# LM7X05-SCH.net
KiCad netlist of a schematic drawn in Altium Designer
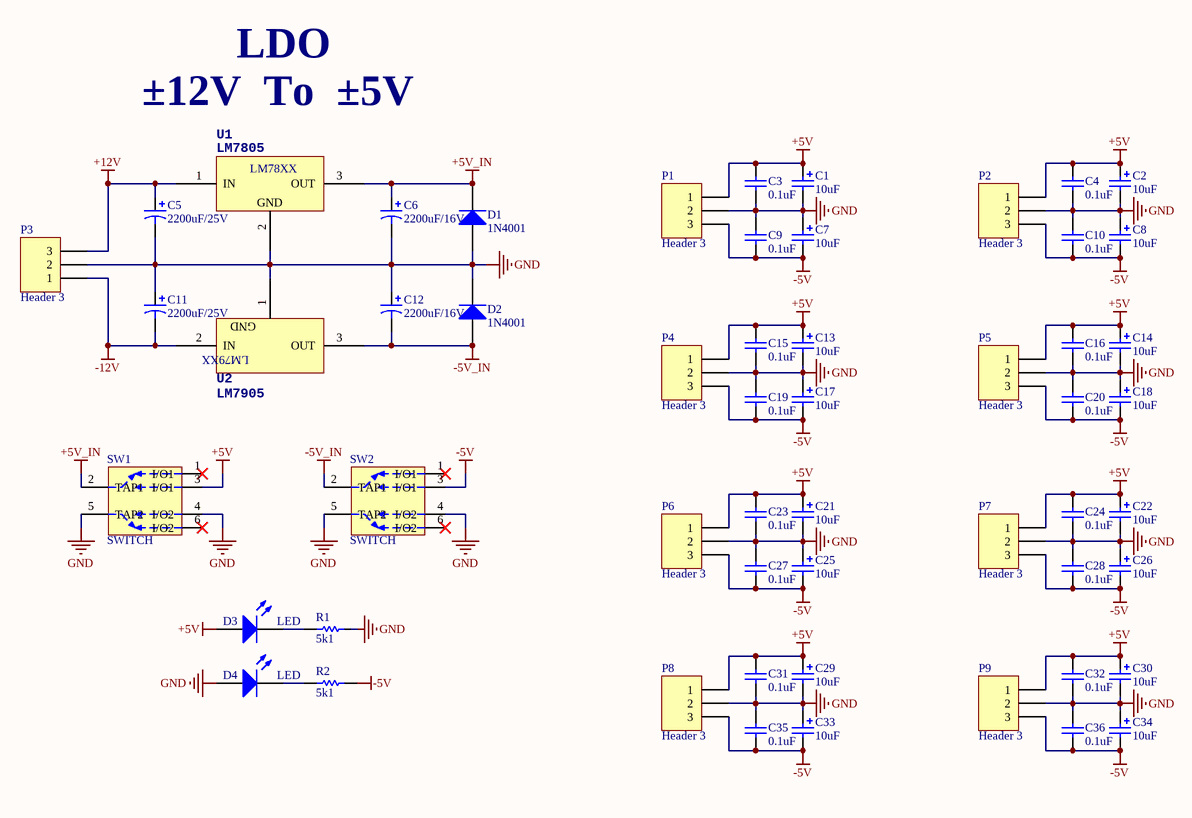
[diagram p0: LM7X05-SCH.SchDoc]

(export (version "E")
  (design (tool "Eeschema 10.0.6"))
  (components
    (comp (ref "C1")
      (value "10uF")
      (footprint "1206T")
      (description "CAP TANT 10UF 10V 10% 1206")
      (fields
        (field (name "MANUFACTURER") "KEMET")
        (field (name "MANUFACTURER PART NUMBER") "T491A106K010AT7280")
      )
      (libsource (lib "Desiger_Schlib") (part "Cap2"))
    )
    (comp (ref "C2")
      (value "10uF")
      (footprint "1206T")
      (description "CAP TANT 10UF 10V 10% 1206")
      (fields
        (field (name "MANUFACTURER") "KEMET")
        (field (name "MANUFACTURER PART NUMBER") "T491A106K010AT7280")
      )
      (libsource (lib "Desiger_Schlib") (part "Cap2"))
    )
    (comp (ref "C3")
      (value "0.1uF")
      (footprint "1206C")
      (description "CAP CER 10000PF 100V X7R 0603")
      (fields
        (field (name "MANUFACTURER") "TDK Corporation")
        (field (name "MANUFACTURER PART NUMBER") "C1608X7R2A103K080AA")
      )
      (libsource (lib "Desiger_Schlib") (part "Cap1"))
    )
    (comp (ref "C4")
      (value "0.1uF")
      (footprint "1206C")
      (description "CAP CER 10000PF 100V X7R 0603")
      (fields
        (field (name "MANUFACTURER") "TDK Corporation")
        (field (name "MANUFACTURER PART NUMBER") "C1608X7R2A103K080AA")
      )
      (libsource (lib "Desiger_Schlib") (part "Cap1"))
    )
    (comp (ref "C5")
      (value "2200uF/25V")
      (footprint "C(16x31)")
      (description "CAP ALUM POLY 150UF 20% 10V SMD")
      (fields
        (field (name "MANUFACTURER") "KEMET")
        (field (name "MANUFACTURER PART NUMBER") "A765EB157M1ALAE022")
      )
      (libsource (lib "Desiger_Schlib") (part "Cap3"))
    )
    (comp (ref "C6")
      (value "2200uF/16V")
      (footprint "C(16x31)")
      (description "CAP ALUM POLY 150UF 20% 10V SMD")
      (fields
        (field (name "MANUFACTURER") "KEMET")
        (field (name "MANUFACTURER PART NUMBER") "A765EB157M1ALAE022")
      )
      (libsource (lib "Desiger_Schlib") (part "Cap3"))
    )
    (comp (ref "C7")
      (value "10uF")
      (footprint "1206T")
      (description "CAP TANT 10UF 10V 10% 1206")
      (fields
        (field (name "MANUFACTURER") "KEMET")
        (field (name "MANUFACTURER PART NUMBER") "T491A106K010AT7280")
      )
      (libsource (lib "Desiger_Schlib") (part "Cap2"))
    )
    (comp (ref "C8")
      (value "10uF")
      (footprint "1206T")
      (description "CAP TANT 10UF 10V 10% 1206")
      (fields
        (field (name "MANUFACTURER") "KEMET")
        (field (name "MANUFACTURER PART NUMBER") "T491A106K010AT7280")
      )
      (libsource (lib "Desiger_Schlib") (part "Cap2"))
    )
    (comp (ref "C9")
      (value "0.1uF")
      (footprint "1206C")
      (description "CAP CER 10000PF 100V X7R 0603")
      (fields
        (field (name "MANUFACTURER") "TDK Corporation")
        (field (name "MANUFACTURER PART NUMBER") "C1608X7R2A103K080AA")
      )
      (libsource (lib "Desiger_Schlib") (part "Cap1"))
    )
    (comp (ref "C10")
      (value "0.1uF")
      (footprint "1206C")
      (description "CAP CER 10000PF 100V X7R 0603")
      (fields
        (field (name "MANUFACTURER") "TDK Corporation")
        (field (name "MANUFACTURER PART NUMBER") "C1608X7R2A103K080AA")
      )
      (libsource (lib "Desiger_Schlib") (part "Cap1"))
    )
    (comp (ref "C11")
      (value "2200uF/25V")
      (footprint "C(16x31)")
      (description "CAP ALUM POLY 150UF 20% 10V SMD")
      (fields
        (field (name "MANUFACTURER") "KEMET")
        (field (name "MANUFACTURER PART NUMBER") "A765EB157M1ALAE022")
      )
      (libsource (lib "Desiger_Schlib") (part "Cap3"))
    )
    (comp (ref "C12")
      (value "2200uF/16V")
      (footprint "C(16x31)")
      (description "CAP ALUM POLY 150UF 20% 10V SMD")
      (fields
        (field (name "MANUFACTURER") "KEMET")
        (field (name "MANUFACTURER PART NUMBER") "A765EB157M1ALAE022")
      )
      (libsource (lib "Desiger_Schlib") (part "Cap3"))
    )
    (comp (ref "C13")
      (value "10uF")
      (footprint "1206T")
      (description "CAP TANT 10UF 10V 10% 1206")
      (fields
        (field (name "MANUFACTURER") "KEMET")
        (field (name "MANUFACTURER PART NUMBER") "T491A106K010AT7280")
      )
      (libsource (lib "Desiger_Schlib") (part "Cap2"))
    )
    (comp (ref "C14")
      (value "10uF")
      (footprint "1206T")
      (description "CAP TANT 10UF 10V 10% 1206")
      (fields
        (field (name "MANUFACTURER") "KEMET")
        (field (name "MANUFACTURER PART NUMBER") "T491A106K010AT7280")
      )
      (libsource (lib "Desiger_Schlib") (part "Cap2"))
    )
    (comp (ref "C15")
      (value "0.1uF")
      (footprint "1206C")
      (description "CAP CER 10000PF 100V X7R 0603")
      (fields
        (field (name "MANUFACTURER") "TDK Corporation")
        (field (name "MANUFACTURER PART NUMBER") "C1608X7R2A103K080AA")
      )
      (libsource (lib "Desiger_Schlib") (part "Cap1"))
    )
    (comp (ref "C16")
      (value "0.1uF")
      (footprint "1206C")
      (description "CAP CER 10000PF 100V X7R 0603")
      (fields
        (field (name "MANUFACTURER") "TDK Corporation")
        (field (name "MANUFACTURER PART NUMBER") "C1608X7R2A103K080AA")
      )
      (libsource (lib "Desiger_Schlib") (part "Cap1"))
    )
    (comp (ref "C17")
      (value "10uF")
      (footprint "1206T")
      (description "CAP TANT 10UF 10V 10% 1206")
      (fields
        (field (name "MANUFACTURER") "KEMET")
        (field (name "MANUFACTURER PART NUMBER") "T491A106K010AT7280")
      )
      (libsource (lib "Desiger_Schlib") (part "Cap2"))
    )
    (comp (ref "C18")
      (value "10uF")
      (footprint "1206T")
      (description "CAP TANT 10UF 10V 10% 1206")
      (fields
        (field (name "MANUFACTURER") "KEMET")
        (field (name "MANUFACTURER PART NUMBER") "T491A106K010AT7280")
      )
      (libsource (lib "Desiger_Schlib") (part "Cap2"))
    )
    (comp (ref "C19")
      (value "0.1uF")
      (footprint "1206C")
      (description "CAP CER 10000PF 100V X7R 0603")
      (fields
        (field (name "MANUFACTURER") "TDK Corporation")
        (field (name "MANUFACTURER PART NUMBER") "C1608X7R2A103K080AA")
      )
      (libsource (lib "Desiger_Schlib") (part "Cap1"))
    )
    (comp (ref "C20")
      (value "0.1uF")
      (footprint "1206C")
      (description "CAP CER 10000PF 100V X7R 0603")
      (fields
        (field (name "MANUFACTURER") "TDK Corporation")
        (field (name "MANUFACTURER PART NUMBER") "C1608X7R2A103K080AA")
      )
      (libsource (lib "Desiger_Schlib") (part "Cap1"))
    )
    (comp (ref "C21")
      (value "10uF")
      (footprint "1206T")
      (description "CAP TANT 10UF 10V 10% 1206")
      (fields
        (field (name "MANUFACTURER") "KEMET")
        (field (name "MANUFACTURER PART NUMBER") "T491A106K010AT7280")
      )
      (libsource (lib "Desiger_Schlib") (part "Cap2"))
    )
    (comp (ref "C22")
      (value "10uF")
      (footprint "1206T")
      (description "CAP TANT 10UF 10V 10% 1206")
      (fields
        (field (name "MANUFACTURER") "KEMET")
        (field (name "MANUFACTURER PART NUMBER") "T491A106K010AT7280")
      )
      (libsource (lib "Desiger_Schlib") (part "Cap2"))
    )
    (comp (ref "C23")
      (value "0.1uF")
      (footprint "1206C")
      (description "CAP CER 10000PF 100V X7R 0603")
      (fields
        (field (name "MANUFACTURER") "TDK Corporation")
        (field (name "MANUFACTURER PART NUMBER") "C1608X7R2A103K080AA")
      )
      (libsource (lib "Desiger_Schlib") (part "Cap1"))
    )
    (comp (ref "C24")
      (value "0.1uF")
      (footprint "1206C")
      (description "CAP CER 10000PF 100V X7R 0603")
      (fields
        (field (name "MANUFACTURER") "TDK Corporation")
        (field (name "MANUFACTURER PART NUMBER") "C1608X7R2A103K080AA")
      )
      (libsource (lib "Desiger_Schlib") (part "Cap1"))
    )
    (comp (ref "C25")
      (value "10uF")
      (footprint "1206T")
      (description "CAP TANT 10UF 10V 10% 1206")
      (fields
        (field (name "MANUFACTURER") "KEMET")
        (field (name "MANUFACTURER PART NUMBER") "T491A106K010AT7280")
      )
      (libsource (lib "Desiger_Schlib") (part "Cap2"))
    )
    (comp (ref "C26")
      (value "10uF")
      (footprint "1206T")
      (description "CAP TANT 10UF 10V 10% 1206")
      (fields
        (field (name "MANUFACTURER") "KEMET")
        (field (name "MANUFACTURER PART NUMBER") "T491A106K010AT7280")
      )
      (libsource (lib "Desiger_Schlib") (part "Cap2"))
    )
    (comp (ref "C27")
      (value "0.1uF")
      (footprint "1206C")
      (description "CAP CER 10000PF 100V X7R 0603")
      (fields
        (field (name "MANUFACTURER") "TDK Corporation")
        (field (name "MANUFACTURER PART NUMBER") "C1608X7R2A103K080AA")
      )
      (libsource (lib "Desiger_Schlib") (part "Cap1"))
    )
    (comp (ref "C28")
      (value "0.1uF")
      (footprint "1206C")
      (description "CAP CER 10000PF 100V X7R 0603")
      (fields
        (field (name "MANUFACTURER") "TDK Corporation")
        (field (name "MANUFACTURER PART NUMBER") "C1608X7R2A103K080AA")
      )
      (libsource (lib "Desiger_Schlib") (part "Cap1"))
    )
    (comp (ref "C29")
      (value "10uF")
      (footprint "1206T")
      (description "CAP TANT 10UF 10V 10% 1206")
      (fields
        (field (name "MANUFACTURER") "KEMET")
        (field (name "MANUFACTURER PART NUMBER") "T491A106K010AT7280")
      )
      (libsource (lib "Desiger_Schlib") (part "Cap2"))
    )
    (comp (ref "C30")
      (value "10uF")
      (footprint "1206T")
      (description "CAP TANT 10UF 10V 10% 1206")
      (fields
        (field (name "MANUFACTURER") "KEMET")
        (field (name "MANUFACTURER PART NUMBER") "T491A106K010AT7280")
      )
      (libsource (lib "Desiger_Schlib") (part "Cap2"))
    )
    (comp (ref "C31")
      (value "0.1uF")
      (footprint "1206C")
      (description "CAP CER 10000PF 100V X7R 0603")
      (fields
        (field (name "MANUFACTURER") "TDK Corporation")
        (field (name "MANUFACTURER PART NUMBER") "C1608X7R2A103K080AA")
      )
      (libsource (lib "Desiger_Schlib") (part "Cap1"))
    )
    (comp (ref "C32")
      (value "0.1uF")
      (footprint "1206C")
      (description "CAP CER 10000PF 100V X7R 0603")
      (fields
        (field (name "MANUFACTURER") "TDK Corporation")
        (field (name "MANUFACTURER PART NUMBER") "C1608X7R2A103K080AA")
      )
      (libsource (lib "Desiger_Schlib") (part "Cap1"))
    )
    (comp (ref "C33")
      (value "10uF")
      (footprint "1206T")
      (description "CAP TANT 10UF 10V 10% 1206")
      (fields
        (field (name "MANUFACTURER") "KEMET")
        (field (name "MANUFACTURER PART NUMBER") "T491A106K010AT7280")
      )
      (libsource (lib "Desiger_Schlib") (part "Cap2"))
    )
    (comp (ref "C34")
      (value "10uF")
      (footprint "1206T")
      (description "CAP TANT 10UF 10V 10% 1206")
      (fields
        (field (name "MANUFACTURER") "KEMET")
        (field (name "MANUFACTURER PART NUMBER") "T491A106K010AT7280")
      )
      (libsource (lib "Desiger_Schlib") (part "Cap2"))
    )
    (comp (ref "C35")
      (value "0.1uF")
      (footprint "1206C")
      (description "CAP CER 10000PF 100V X7R 0603")
      (fields
        (field (name "MANUFACTURER") "TDK Corporation")
        (field (name "MANUFACTURER PART NUMBER") "C1608X7R2A103K080AA")
      )
      (libsource (lib "Desiger_Schlib") (part "Cap1"))
    )
    (comp (ref "C36")
      (value "0.1uF")
      (footprint "1206C")
      (description "CAP CER 10000PF 100V X7R 0603")
      (fields
        (field (name "MANUFACTURER") "TDK Corporation")
        (field (name "MANUFACTURER PART NUMBER") "C1608X7R2A103K080AA")
      )
      (libsource (lib "Desiger_Schlib") (part "Cap1"))
    )
    (comp (ref "D1")
      (value "1N4001")
      (footprint "DIODE-10R0X2R5-1R2")
      (description "Default Diode")
      (fields (field (name "PUBLISHER") "Altium Limited"))
      (libsource (lib "Desiger_Schlib") (part "Diode"))
    )
    (comp (ref "D2")
      (value "1N4001")
      (footprint "DIODE-10R0X2R5-1R2")
      (description "Default Diode")
      (fields (field (name "PUBLISHER") "Altium Limited"))
      (libsource (lib "Desiger_Schlib") (part "Diode"))
    )
    (comp (ref "D3")
      (value "LED")
      (footprint "0603D")
      (description "Typical RED GaAs LED")
      (fields (field (name "PUBLISHER") "Altium Limited"))
      (libsource (lib "Desiger_Schlib") (part "LED"))
    )
    (comp (ref "D4")
      (value "LED")
      (footprint "0603D")
      (description "Typical RED GaAs LED")
      (fields (field (name "PUBLISHER") "Altium Limited"))
      (libsource (lib "Desiger_Schlib") (part "LED"))
    )
    (comp (ref "P1")
      (value "Header 3")
      (footprint "KF2EDG_3R81_3P")
      (description "Header, 3-Pin")
      (fields (field (name "PUBLISHER") "Altium Limited"))
      (libsource (lib "") (part "Header 3_1"))
    )
    (comp (ref "P2")
      (value "Header 3")
      (footprint "KF2EDG_3R81_3P")
      (description "Header, 3-Pin")
      (fields (field (name "PUBLISHER") "Altium Limited"))
      (libsource (lib "") (part "Header 3_1"))
    )
    (comp (ref "P3")
      (value "Header 3")
      (footprint "KF2EDG_3R81_3P")
      (description "Header, 3-Pin")
      (fields (field (name "PUBLISHER") "Altium Limited"))
      (libsource (lib "Miscellaneous Connectors") (part "Header 3"))
    )
    (comp (ref "P4")
      (value "Header 3")
      (footprint "KF2EDG_3R81_3P")
      (description "Header, 3-Pin")
      (fields (field (name "PUBLISHER") "Altium Limited"))
      (libsource (lib "") (part "Header 3_1"))
    )
    (comp (ref "P5")
      (value "Header 3")
      (footprint "KF2EDG_3R81_3P")
      (description "Header, 3-Pin")
      (fields (field (name "PUBLISHER") "Altium Limited"))
      (libsource (lib "") (part "Header 3_1"))
    )
    (comp (ref "P6")
      (value "Header 3")
      (footprint "KF2EDG_3R81_3P")
      (description "Header, 3-Pin")
      (fields (field (name "PUBLISHER") "Altium Limited"))
      (libsource (lib "") (part "Header 3_1"))
    )
    (comp (ref "P7")
      (value "Header 3")
      (footprint "KF2EDG_3R81_3P")
      (description "Header, 3-Pin")
      (fields (field (name "PUBLISHER") "Altium Limited"))
      (libsource (lib "") (part "Header 3_1"))
    )
    (comp (ref "P8")
      (value "Header 3")
      (footprint "KF2EDG_3R81_3P")
      (description "Header, 3-Pin")
      (fields (field (name "PUBLISHER") "Altium Limited"))
      (libsource (lib "") (part "Header 3_1"))
    )
    (comp (ref "P9")
      (value "Header 3")
      (footprint "KF2EDG_3R81_3P")
      (description "Header, 3-Pin")
      (fields (field (name "PUBLISHER") "Altium Limited"))
      (libsource (lib "") (part "Header 3_1"))
    )
    (comp (ref "R1")
      (value "5k1")
      (footprint "R0603")
      (description "RES SMD 1K OHM 0.5% 1/16W 0603")
      (fields
        (field (name "MANUFACTURER") "Susumu")
        (field (name "MANUFACTURER PART NUMBER") "RR0816P-102-D")
      )
      (libsource (lib "Desiger_Schlib") (part "Res1"))
    )
    (comp (ref "R2")
      (value "5k1")
      (footprint "R0603")
      (description "RES SMD 1K OHM 0.5% 1/16W 0603")
      (fields
        (field (name "MANUFACTURER") "Susumu")
        (field (name "MANUFACTURER PART NUMBER") "RR0816P-102-D")
      )
      (libsource (lib "Desiger_Schlib") (part "Res1"))
    )
    (comp (ref "SW1")
      (value "SWITCH")
      (footprint "Desiger_Pcblib:SW-8R5X8R5")
      (libsource (lib "Desiger_Schlib") (part "SWITCH"))
    )
    (comp (ref "SW2")
      (value "SWITCH")
      (footprint "Desiger_Pcblib:SW-8R5X8R5")
      (libsource (lib "Desiger_Schlib") (part "SWITCH"))
    )
    (comp (ref "U1")
      (value "LM7805")
      (footprint "TO-220B")
      (description "LM78XX")
      (libsource (lib "Desiger_Schlib") (part "LM78XX"))
    )
    (comp (ref "U2")
      (value "LM7905")
      (footprint "TO-220B")
      (description "LM79XX")
      (libsource (lib "Desiger_Schlib") (part "LM79XX"))
    )
  )
  (nets
    (net (code "1") (name "+5V") (class "Default")
      (node (ref "C1") (pin "1") (pinfunction "+_1") (pintype "passive"))
      (node (ref "C13") (pin "1") (pinfunction "+_1") (pintype "passive"))
      (node (ref "C14") (pin "1") (pinfunction "+_1") (pintype "passive"))
      (node (ref "C15") (pin "2") (pinfunction "2_2") (pintype "passive"))
      (node (ref "C16") (pin "2") (pinfunction "2_2") (pintype "passive"))
      (node (ref "C2") (pin "1") (pinfunction "+_1") (pintype "passive"))
      (node (ref "C21") (pin "1") (pinfunction "+_1") (pintype "passive"))
      (node (ref "C22") (pin "1") (pinfunction "+_1") (pintype "passive"))
      (node (ref "C23") (pin "2") (pinfunction "2_2") (pintype "passive"))
      (node (ref "C24") (pin "2") (pinfunction "2_2") (pintype "passive"))
      (node (ref "C29") (pin "1") (pinfunction "+_1") (pintype "passive"))
      (node (ref "C3") (pin "2") (pinfunction "2_2") (pintype "passive"))
      (node (ref "C30") (pin "1") (pinfunction "+_1") (pintype "passive"))
      (node (ref "C31") (pin "2") (pinfunction "2_2") (pintype "passive"))
      (node (ref "C32") (pin "2") (pinfunction "2_2") (pintype "passive"))
      (node (ref "C4") (pin "2") (pinfunction "2_2") (pintype "passive"))
      (node (ref "D3") (pin "1") (pinfunction "A_1") (pintype "passive"))
      (node (ref "P1") (pin "1") (pinfunction "1_1") (pintype "passive"))
      (node (ref "P2") (pin "1") (pinfunction "1_1") (pintype "passive"))
      (node (ref "P4") (pin "1") (pinfunction "1_1") (pintype "passive"))
      (node (ref "P5") (pin "1") (pinfunction "1_1") (pintype "passive"))
      (node (ref "P6") (pin "1") (pinfunction "1_1") (pintype "passive"))
      (node (ref "P7") (pin "1") (pinfunction "1_1") (pintype "passive"))
      (node (ref "P8") (pin "1") (pinfunction "1_1") (pintype "passive"))
      (node (ref "P9") (pin "1") (pinfunction "1_1") (pintype "passive"))
      (node (ref "SW1") (pin "3") (pinfunction "I/O1_3") (pintype "passive"))
    )
    (net (code "2") (name "+5V_IN") (class "Default")
      (node (ref "C6") (pin "1") (pinfunction "+_1") (pintype "passive"))
      (node (ref "D1") (pin "2") (pinfunction "K_2") (pintype "passive"))
      (node (ref "SW1") (pin "2") (pinfunction "TAP1_2") (pintype "passive"))
      (node (ref "U1") (pin "3") (pinfunction "OUT_3") (pintype "passive"))
    )
    (net (code "3") (name "+12V") (class "Default")
      (node (ref "C5") (pin "1") (pinfunction "+_1") (pintype "passive"))
      (node (ref "P3") (pin "3") (pinfunction "3_3") (pintype "passive"))
      (node (ref "U1") (pin "1") (pinfunction "IN_1") (pintype "passive"))
    )
    (net (code "4") (name "-5V") (class "Default")
      (node (ref "C10") (pin "1") (pinfunction "1_1") (pintype "passive"))
      (node (ref "C17") (pin "2") (pinfunction "-_2") (pintype "passive"))
      (node (ref "C18") (pin "2") (pinfunction "-_2") (pintype "passive"))
      (node (ref "C19") (pin "1") (pinfunction "1_1") (pintype "passive"))
      (node (ref "C20") (pin "1") (pinfunction "1_1") (pintype "passive"))
      (node (ref "C25") (pin "2") (pinfunction "-_2") (pintype "passive"))
      (node (ref "C26") (pin "2") (pinfunction "-_2") (pintype "passive"))
      (node (ref "C27") (pin "1") (pinfunction "1_1") (pintype "passive"))
      (node (ref "C28") (pin "1") (pinfunction "1_1") (pintype "passive"))
      (node (ref "C33") (pin "2") (pinfunction "-_2") (pintype "passive"))
      (node (ref "C34") (pin "2") (pinfunction "-_2") (pintype "passive"))
      (node (ref "C35") (pin "1") (pinfunction "1_1") (pintype "passive"))
      (node (ref "C36") (pin "1") (pinfunction "1_1") (pintype "passive"))
      (node (ref "C7") (pin "2") (pinfunction "-_2") (pintype "passive"))
      (node (ref "C8") (pin "2") (pinfunction "-_2") (pintype "passive"))
      (node (ref "C9") (pin "1") (pinfunction "1_1") (pintype "passive"))
      (node (ref "P1") (pin "3") (pinfunction "3_3") (pintype "passive"))
      (node (ref "P2") (pin "3") (pinfunction "3_3") (pintype "passive"))
      (node (ref "P4") (pin "3") (pinfunction "3_3") (pintype "passive"))
      (node (ref "P5") (pin "3") (pinfunction "3_3") (pintype "passive"))
      (node (ref "P6") (pin "3") (pinfunction "3_3") (pintype "passive"))
      (node (ref "P7") (pin "3") (pinfunction "3_3") (pintype "passive"))
      (node (ref "P8") (pin "3") (pinfunction "3_3") (pintype "passive"))
      (node (ref "P9") (pin "3") (pinfunction "3_3") (pintype "passive"))
      (node (ref "R2") (pin "2") (pinfunction "2_2") (pintype "passive"))
      (node (ref "SW2") (pin "3") (pinfunction "I/O1_3") (pintype "passive"))
    )
    (net (code "5") (name "-5V_IN") (class "Default")
      (node (ref "C12") (pin "2") (pinfunction "-_2") (pintype "passive"))
      (node (ref "D2") (pin "1") (pinfunction "A_1") (pintype "passive"))
      (node (ref "SW2") (pin "2") (pinfunction "TAP1_2") (pintype "passive"))
      (node (ref "U2") (pin "3") (pinfunction "OUT_3") (pintype "passive"))
    )
    (net (code "6") (name "-12V") (class "Default")
      (node (ref "C11") (pin "2") (pinfunction "-_2") (pintype "passive"))
      (node (ref "P3") (pin "1") (pinfunction "1_1") (pintype "passive"))
      (node (ref "U2") (pin "2") (pinfunction "IN_2") (pintype "passive"))
    )
    (net (code "7") (name "GND") (class "Default")
      (node (ref "C1") (pin "2") (pinfunction "-_2") (pintype "passive"))
      (node (ref "C10") (pin "2") (pinfunction "2_2") (pintype "passive"))
      (node (ref "C11") (pin "1") (pinfunction "+_1") (pintype "passive"))
      (node (ref "C12") (pin "1") (pinfunction "+_1") (pintype "passive"))
      (node (ref "C13") (pin "2") (pinfunction "-_2") (pintype "passive"))
      (node (ref "C14") (pin "2") (pinfunction "-_2") (pintype "passive"))
      (node (ref "C15") (pin "1") (pinfunction "1_1") (pintype "passive"))
      (node (ref "C16") (pin "1") (pinfunction "1_1") (pintype "passive"))
      (node (ref "C17") (pin "1") (pinfunction "+_1") (pintype "passive"))
      (node (ref "C18") (pin "1") (pinfunction "+_1") (pintype "passive"))
      (node (ref "C19") (pin "2") (pinfunction "2_2") (pintype "passive"))
      (node (ref "C2") (pin "2") (pinfunction "-_2") (pintype "passive"))
      (node (ref "C20") (pin "2") (pinfunction "2_2") (pintype "passive"))
      (node (ref "C21") (pin "2") (pinfunction "-_2") (pintype "passive"))
      (node (ref "C22") (pin "2") (pinfunction "-_2") (pintype "passive"))
      (node (ref "C23") (pin "1") (pinfunction "1_1") (pintype "passive"))
      (node (ref "C24") (pin "1") (pinfunction "1_1") (pintype "passive"))
      (node (ref "C25") (pin "1") (pinfunction "+_1") (pintype "passive"))
      (node (ref "C26") (pin "1") (pinfunction "+_1") (pintype "passive"))
      (node (ref "C27") (pin "2") (pinfunction "2_2") (pintype "passive"))
      (node (ref "C28") (pin "2") (pinfunction "2_2") (pintype "passive"))
      (node (ref "C29") (pin "2") (pinfunction "-_2") (pintype "passive"))
      (node (ref "C3") (pin "1") (pinfunction "1_1") (pintype "passive"))
      (node (ref "C30") (pin "2") (pinfunction "-_2") (pintype "passive"))
      (node (ref "C31") (pin "1") (pinfunction "1_1") (pintype "passive"))
      (node (ref "C32") (pin "1") (pinfunction "1_1") (pintype "passive"))
      (node (ref "C33") (pin "1") (pinfunction "+_1") (pintype "passive"))
      (node (ref "C34") (pin "1") (pinfunction "+_1") (pintype "passive"))
      (node (ref "C35") (pin "2") (pinfunction "2_2") (pintype "passive"))
      (node (ref "C36") (pin "2") (pinfunction "2_2") (pintype "passive"))
      (node (ref "C4") (pin "1") (pinfunction "1_1") (pintype "passive"))
      (node (ref "C5") (pin "2") (pinfunction "-_2") (pintype "passive"))
      (node (ref "C6") (pin "2") (pinfunction "-_2") (pintype "passive"))
      (node (ref "C7") (pin "1") (pinfunction "+_1") (pintype "passive"))
      (node (ref "C8") (pin "1") (pinfunction "+_1") (pintype "passive"))
      (node (ref "C9") (pin "2") (pinfunction "2_2") (pintype "passive"))
      (node (ref "D1") (pin "1") (pinfunction "A_1") (pintype "passive"))
      (node (ref "D2") (pin "2") (pinfunction "K_2") (pintype "passive"))
      (node (ref "D4") (pin "1") (pinfunction "A_1") (pintype "passive"))
      (node (ref "P1") (pin "2") (pinfunction "2_2") (pintype "passive"))
      (node (ref "P2") (pin "2") (pinfunction "2_2") (pintype "passive"))
      (node (ref "P3") (pin "2") (pinfunction "2_2") (pintype "passive"))
      (node (ref "P4") (pin "2") (pinfunction "2_2") (pintype "passive"))
      (node (ref "P5") (pin "2") (pinfunction "2_2") (pintype "passive"))
      (node (ref "P6") (pin "2") (pinfunction "2_2") (pintype "passive"))
      (node (ref "P7") (pin "2") (pinfunction "2_2") (pintype "passive"))
      (node (ref "P8") (pin "2") (pinfunction "2_2") (pintype "passive"))
      (node (ref "P9") (pin "2") (pinfunction "2_2") (pintype "passive"))
      (node (ref "R1") (pin "2") (pinfunction "2_2") (pintype "passive"))
      (node (ref "SW1") (pin "4") (pinfunction "I/O2_4") (pintype "passive"))
      (node (ref "SW1") (pin "5") (pinfunction "TAP2_5") (pintype "passive"))
      (node (ref "SW2") (pin "4") (pinfunction "I/O2_4") (pintype "passive"))
      (node (ref "SW2") (pin "5") (pinfunction "TAP2_5") (pintype "passive"))
      (node (ref "U1") (pin "2") (pinfunction "GND_2") (pintype "passive"))
      (node (ref "U2") (pin "1") (pinfunction "GND_1") (pintype "passive"))
    )
    (net (code "8") (name "Net-(D3-K)") (class "Default")
      (node (ref "D3") (pin "2") (pinfunction "K_2") (pintype "passive"))
      (node (ref "R1") (pin "1") (pinfunction "1_1") (pintype "passive"))
    )
    (net (code "9") (name "Net-(D4-K)") (class "Default")
      (node (ref "D4") (pin "2") (pinfunction "K_2") (pintype "passive"))
      (node (ref "R2") (pin "1") (pinfunction "1_1") (pintype "passive"))
    )
    (net (code "10") (name "unconnected-(SW1-I{slash}O1-Pad1)") (class "Default")
      (node (ref "SW1") (pin "1") (pinfunction "I/O1_1") (pintype "passive+no_connect"))
    )
    (net (code "11") (name "unconnected-(SW1-I{slash}O2-Pad6)") (class "Default")
      (node (ref "SW1") (pin "6") (pinfunction "I/O2_6") (pintype "passive+no_connect"))
    )
    (net (code "12") (name "unconnected-(SW2-I{slash}O1-Pad1)") (class "Default")
      (node (ref "SW2") (pin "1") (pinfunction "I/O1_1") (pintype "passive+no_connect"))
    )
    (net (code "13") (name "unconnected-(SW2-I{slash}O2-Pad6)") (class "Default")
      (node (ref "SW2") (pin "6") (pinfunction "I/O2_6") (pintype "passive+no_connect"))
    )
  )
)
